# MCU_Sensors_CAN.net
KiCad netlist of a schematic drawn in Altium Designer
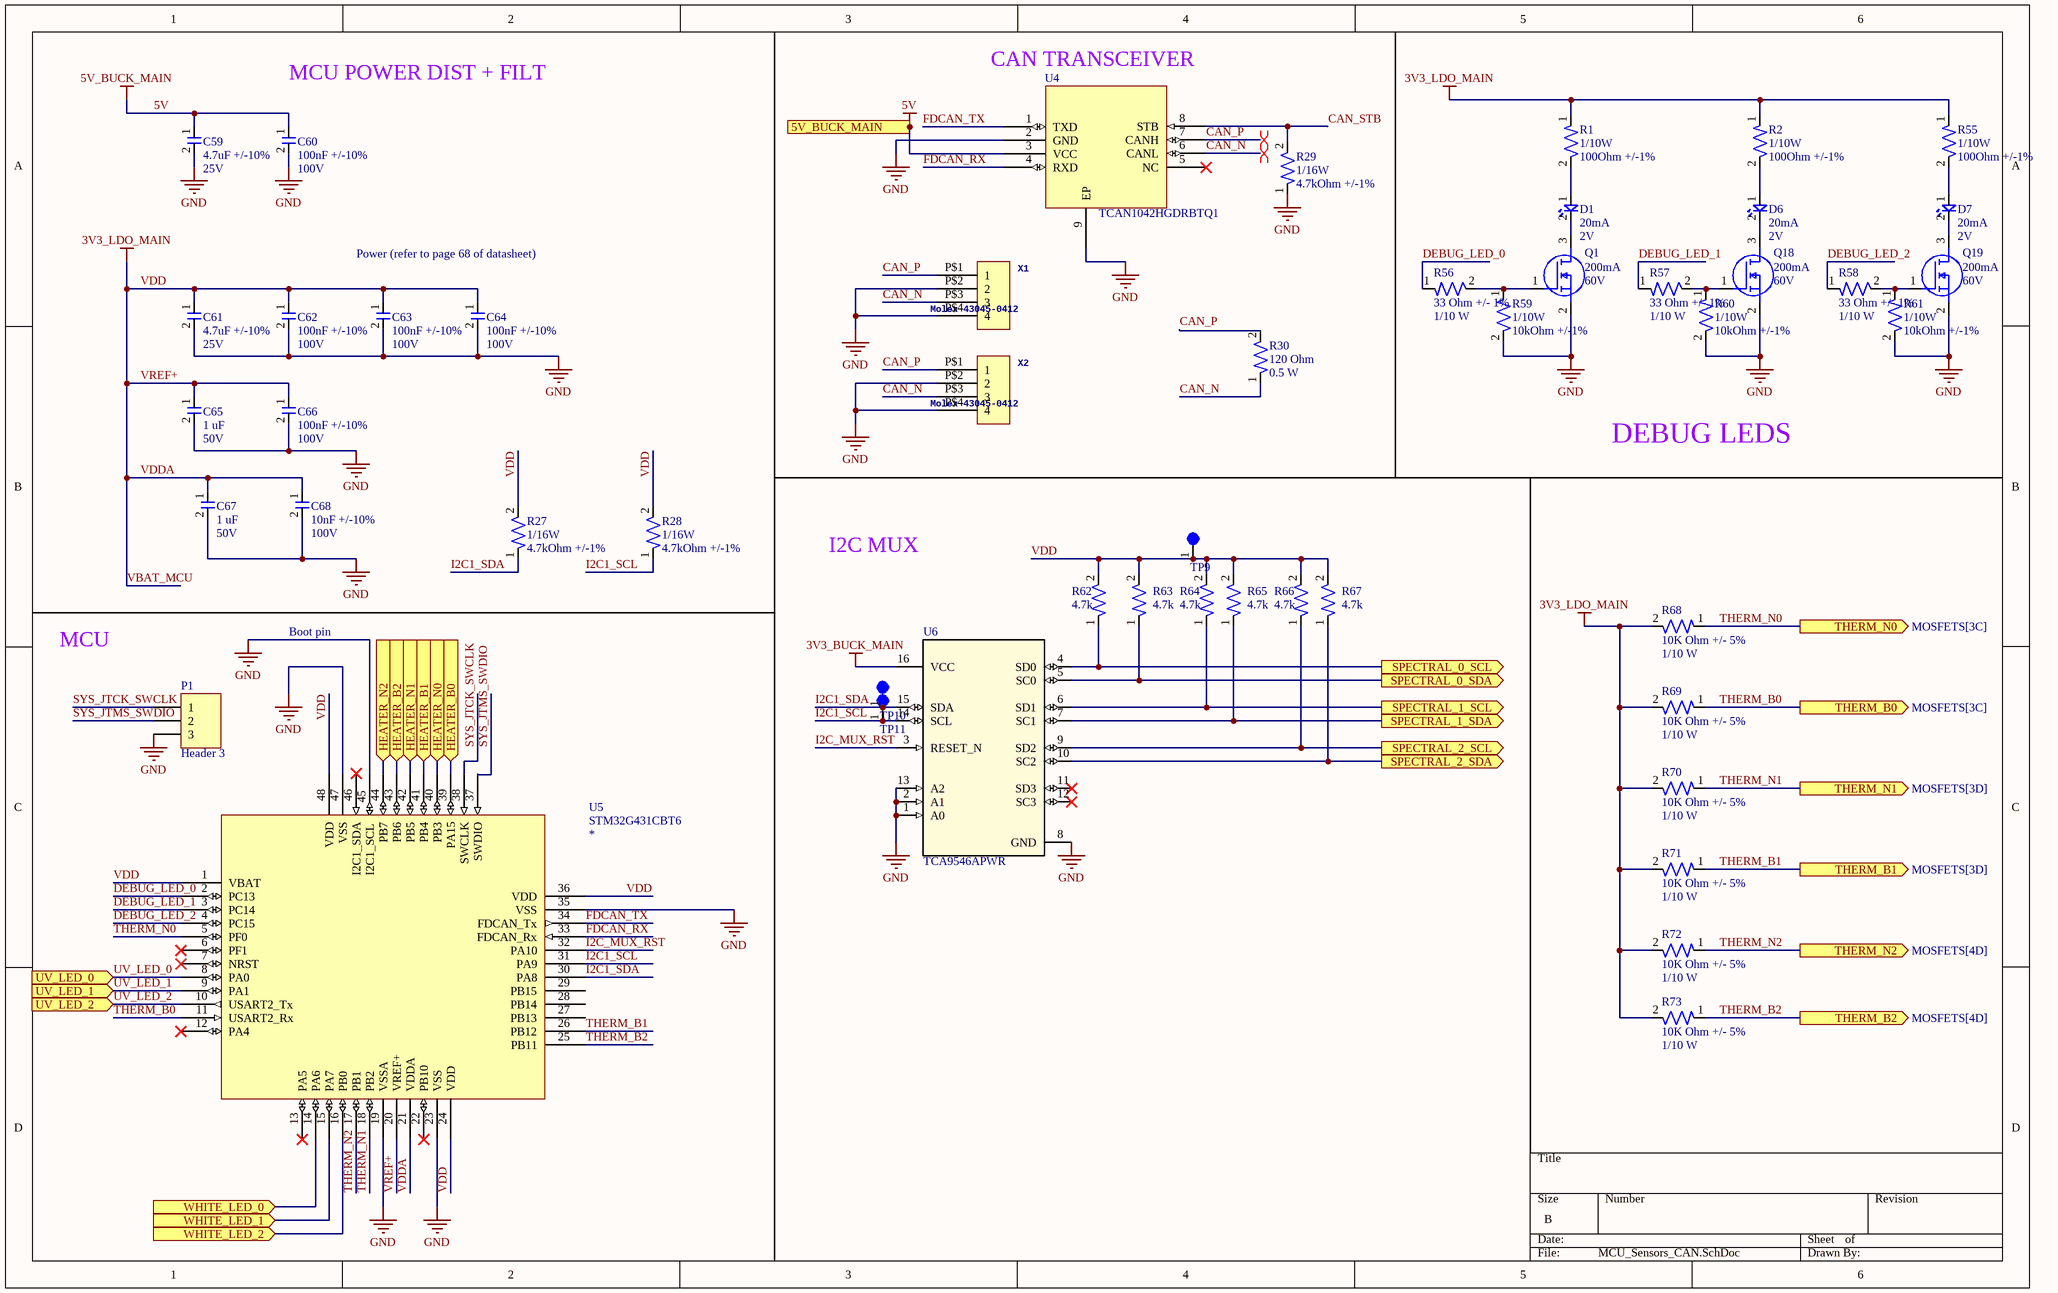
[diagram p0: MCU_Sensors_CAN.SchDoc]

(export (version "E")
  (design (tool "Eeschema 10.0.6"))
  (components
    (comp (ref "C59")
      (value "TMK107BBJ475KA-T")
      (footprint "CAP-0603")
      (description "4.7 µF ±10% 25V Ceramic Capacitor X5R 0603 (1608 Metric)")
      (fields
        (field (name "MANUFACTURER") "Taiyo Yuden")
        (field (name "CAPACITANCE") "4.7uF +/-10%")
        (field (name "VOLTAGE RATING") "25V")
      )
      (libsource (lib "MasterLib") (part "CAP-4.7U-0001"))
    )
    (comp (ref "C60")
      (value "CC0603KRX7R0BB104")
      (footprint "CAP-0603")
      (description "CAP CER 0.1UF 100V X7R 0603")
      (fields
        (field (name "MANUFACTURER") "YAGEO")
        (field (name "CAPACITANCE") "100nF +/-10%")
        (field (name "VOLTAGE RATING") "100V")
      )
      (libsource (lib "MasterLib") (part "CAP-100N-0001"))
    )
    (comp (ref "C61")
      (value "TMK107BBJ475KA-T")
      (footprint "CAP-0603")
      (description "4.7 µF ±10% 25V Ceramic Capacitor X5R 0603 (1608 Metric)")
      (fields
        (field (name "MANUFACTURER") "Taiyo Yuden")
        (field (name "CAPACITANCE") "4.7uF +/-10%")
        (field (name "VOLTAGE RATING") "25V")
      )
      (libsource (lib "MasterLib") (part "CAP-4.7U-0001"))
    )
    (comp (ref "C62")
      (value "CC0603KRX7R0BB104")
      (footprint "CAP-0603")
      (description "CAP CER 0.1UF 100V X7R 0603")
      (fields
        (field (name "MANUFACTURER") "YAGEO")
        (field (name "CAPACITANCE") "100nF +/-10%")
        (field (name "VOLTAGE RATING") "100V")
      )
      (libsource (lib "MasterLib") (part "CAP-100N-0001"))
    )
    (comp (ref "C63")
      (value "CC0603KRX7R0BB104")
      (footprint "CAP-0603")
      (description "CAP CER 0.1UF 100V X7R 0603")
      (fields
        (field (name "MANUFACTURER") "YAGEO")
        (field (name "CAPACITANCE") "100nF +/-10%")
        (field (name "VOLTAGE RATING") "100V")
      )
      (libsource (lib "MasterLib") (part "CAP-100N-0001"))
    )
    (comp (ref "C64")
      (value "CC0603KRX7R0BB104")
      (footprint "CAP-0603")
      (description "CAP CER 0.1UF 100V X7R 0603")
      (fields
        (field (name "MANUFACTURER") "YAGEO")
        (field (name "CAPACITANCE") "100nF +/-10%")
        (field (name "VOLTAGE RATING") "100V")
      )
      (libsource (lib "MasterLib") (part "CAP-100N-0001"))
    )
    (comp (ref "C65")
      (value "UMK107AB7105KA-T")
      (footprint "CAP-0603")
      (description "1 µF ±10% 50V Ceramic Capacitor X7R 0603 (1608 Metric)")
      (fields (field (name "CAPACITANCE") "1 uF") (field (name "VOLTAGE") "50V"))
      (libsource (lib "MasterLib") (part "CAP-1U-0002"))
    )
    (comp (ref "C66")
      (value "CC0603KRX7R0BB104")
      (footprint "CAP-0603")
      (description "CAP CER 0.1UF 100V X7R 0603")
      (fields
        (field (name "MANUFACTURER") "YAGEO")
        (field (name "CAPACITANCE") "100nF +/-10%")
        (field (name "VOLTAGE RATING") "100V")
      )
      (libsource (lib "MasterLib") (part "CAP-100N-0001"))
    )
    (comp (ref "C67")
      (value "UMK107AB7105KA-T")
      (footprint "CAP-0603")
      (description "1 µF ±10% 50V Ceramic Capacitor X7R 0603 (1608 Metric)")
      (fields (field (name "CAPACITANCE") "1 uF") (field (name "VOLTAGE") "50V"))
      (libsource (lib "MasterLib") (part "CAP-1U-0002"))
    )
    (comp (ref "C68")
      (value "CC0402KRX7R0BB103")
      (footprint "CAP-0402")
      (description "10000 pF ±10% 100V Ceramic Capacitor X7R 0402 (1005 Metric)")
      (fields
        (field (name "MANUFACTURER") "YAGEO")
        (field (name "CAPACITANCE") "10nF +/-10%")
        (field (name "VOLTAGE RATING") "100V")
      )
      (libsource (lib "MasterLib") (part "CAP-10N-0001"))
    )
    (comp (ref "D1")
      (value "150060AS75000")
      (footprint "LED-0603")
      (description "CAP CER 0.1UF 100V X7R 0603")
      (fields
        (field (name "MANUFACTURER") "Wurth Electronik")
        (field (name "CURRENT RATING") "20mA")
        (field (name "VF") "2V")
      )
      (libsource (lib "MasterLib") (part "LED_Amber_0001"))
    )
    (comp (ref "D6")
      (value "150060AS75000")
      (footprint "LED-0603")
      (description "CAP CER 0.1UF 100V X7R 0603")
      (fields
        (field (name "MANUFACTURER") "Wurth Electronik")
        (field (name "CURRENT RATING") "20mA")
        (field (name "VF") "2V")
      )
      (libsource (lib "MasterLib") (part "LED_Amber_0001"))
    )
    (comp (ref "D7")
      (value "150060AS75000")
      (footprint "LED-0603")
      (description "CAP CER 0.1UF 100V X7R 0603")
      (fields
        (field (name "MANUFACTURER") "Wurth Electronik")
        (field (name "CURRENT RATING") "20mA")
        (field (name "VF") "2V")
      )
      (libsource (lib "MasterLib") (part "LED_Amber_0001"))
    )
    (comp (ref "P1")
      (value "Header 3")
      (footprint "HDR1X3")
      (description "Header, 3-Pin")
      (fields (field (name "PUBLISHER") "Altium Limited"))
      (libsource (lib "Miscellaneous Connectors") (part "Header 3"))
    )
    (comp (ref "Q1")
      (value "T2N7002AK,LM")
      (footprint "NMOS-SOT23-3")
      (description "MOSFET N-CH 60V 200MA SOT23")
      (fields
        (field (name "MANUFACTURER") "Toshiba")
        (field (name "ID-CONTINUOUS") "200mA")
        (field (name "VDS-MAX") "60V")
      )
      (libsource (lib "MasterLib") (part "NMOS-200MA-0001"))
    )
    (comp (ref "Q18")
      (value "T2N7002AK,LM")
      (footprint "NMOS-SOT23-3")
      (description "MOSFET N-CH 60V 200MA SOT23")
      (fields
        (field (name "MANUFACTURER") "Toshiba")
        (field (name "ID-CONTINUOUS") "200mA")
        (field (name "VDS-MAX") "60V")
      )
      (libsource (lib "MasterLib") (part "NMOS-200MA-0001"))
    )
    (comp (ref "Q19")
      (value "T2N7002AK,LM")
      (footprint "NMOS-SOT23-3")
      (description "MOSFET N-CH 60V 200MA SOT23")
      (fields
        (field (name "MANUFACTURER") "Toshiba")
        (field (name "ID-CONTINUOUS") "200mA")
        (field (name "VDS-MAX") "60V")
      )
      (libsource (lib "MasterLib") (part "NMOS-200MA-0001"))
    )
    (comp (ref "R1")
      (value "AC0603FR-10100RL")
      (footprint "RES-0603")
      (description "100 Ohms ±1% 0.1W, 1/10W Chip Resistor 0603 (1608 Metric) Automotive AEC-Q200 Thick Film")
      (fields
        (field (name "MANUFACTURER") "YAGEO")
        (field (name "POWER RATING") "1/10W")
        (field (name "RESISTANCE") "100Ohm +/-1%")
      )
      (libsource (lib "MasterLib") (part "RES-100-0002"))
    )
    (comp (ref "R2")
      (value "AC0603FR-10100RL")
      (footprint "RES-0603")
      (description "100 Ohms ±1% 0.1W, 1/10W Chip Resistor 0603 (1608 Metric) Automotive AEC-Q200 Thick Film")
      (fields
        (field (name "MANUFACTURER") "YAGEO")
        (field (name "POWER RATING") "1/10W")
        (field (name "RESISTANCE") "100Ohm +/-1%")
      )
      (libsource (lib "MasterLib") (part "RES-100-0002"))
    )
    (comp (ref "R27")
      (value "RC0402FR-074K7P")
      (footprint "RES-0402")
      (description "RES SMD 4.7K OHM 1% 1/16W 0402")
      (fields
        (field (name "MANUFACTURER") "YAGEO")
        (field (name "POWER RATING") "1/16W")
        (field (name "RESISTANCE") "4.7kOhm +/-1%")
      )
      (libsource (lib "MasterLib") (part "RES-4.7K-0001"))
    )
    (comp (ref "R28")
      (value "RC0402FR-074K7P")
      (footprint "RES-0402")
      (description "RES SMD 4.7K OHM 1% 1/16W 0402")
      (fields
        (field (name "MANUFACTURER") "YAGEO")
        (field (name "POWER RATING") "1/16W")
        (field (name "RESISTANCE") "4.7kOhm +/-1%")
      )
      (libsource (lib "MasterLib") (part "RES-4.7K-0001"))
    )
    (comp (ref "R29")
      (value "RC0402FR-074K7P")
      (footprint "RES-0402")
      (description "RES SMD 4.7K OHM 1% 1/16W 0402")
      (fields
        (field (name "MANUFACTURER") "YAGEO")
        (field (name "POWER RATING") "1/16W")
        (field (name "RESISTANCE") "4.7kOhm +/-1%")
      )
      (libsource (lib "MasterLib") (part "RES-4.7K-0001"))
    )
    (comp (ref "R30")
      (value "CRGH1206F120R")
      (footprint "RES-1206")
      (description "120 Ohms ±1% 0.5W, 1/2W Chip Resistor 1206 (3216 Metric) Thick Film")
      (fields
        (field (name "TOLERANCE") "1%")
        (field (name "RESISTANCE") "120 Ohm")
        (field (name "POWER") "0.5 W")
      )
      (libsource (lib "MasterLib") (part "RES-120-0002"))
    )
    (comp (ref "R55")
      (value "AC0603FR-10100RL")
      (footprint "RES-0603")
      (description "100 Ohms ±1% 0.1W, 1/10W Chip Resistor 0603 (1608 Metric) Automotive AEC-Q200 Thick Film")
      (fields
        (field (name "MANUFACTURER") "YAGEO")
        (field (name "POWER RATING") "1/10W")
        (field (name "RESISTANCE") "100Ohm +/-1%")
      )
      (libsource (lib "MasterLib") (part "RES-100-0002"))
    )
    (comp (ref "R56")
      (value "ERJ2RKF33R0X")
      (footprint "RES-0402")
      (description "100mW Thick Film Resistors ±100ppm/℃ ±1% -55℃~+155℃ 33Ω 0402  Chip Resistor - Surface Mount ROHS")
      (fields
        (field (name "RESISTANCE") "33 Ohm +/- 1%")
        (field (name "POWER") "1/10 W")
        (field (name "JLC PART NUMBER") "C278594")
      )
      (libsource (lib "MasterLib") (part "RES-33-0003-JLC"))
    )
    (comp (ref "R57")
      (value "ERJ2RKF33R0X")
      (footprint "RES-0402")
      (description "100mW Thick Film Resistors ±100ppm/℃ ±1% -55℃~+155℃ 33Ω 0402  Chip Resistor - Surface Mount ROHS")
      (fields
        (field (name "RESISTANCE") "33 Ohm +/- 1%")
        (field (name "POWER") "1/10 W")
        (field (name "JLC PART NUMBER") "C278594")
      )
      (libsource (lib "MasterLib") (part "RES-33-0003-JLC"))
    )
    (comp (ref "R58")
      (value "ERJ2RKF33R0X")
      (footprint "RES-0402")
      (description "100mW Thick Film Resistors ±100ppm/℃ ±1% -55℃~+155℃ 33Ω 0402  Chip Resistor - Surface Mount ROHS")
      (fields
        (field (name "RESISTANCE") "33 Ohm +/- 1%")
        (field (name "POWER") "1/10 W")
        (field (name "JLC PART NUMBER") "C278594")
      )
      (libsource (lib "MasterLib") (part "RES-33-0003-JLC"))
    )
    (comp (ref "R59")
      (value "RC0603FR-0710KP")
      (footprint "RES-0603")
      (description "RES SMD 10K OHM 1% 1/10W 0603")
      (fields
        (field (name "MANUFACTURER") "YAGEO")
        (field (name "POWER RATING") "1/10W")
        (field (name "RESISTANCE") "10kOhm +/-1%")
      )
      (libsource (lib "MasterLib") (part "RES-10K-0002"))
    )
    (comp (ref "R60")
      (value "RC0603FR-0710KP")
      (footprint "RES-0603")
      (description "RES SMD 10K OHM 1% 1/10W 0603")
      (fields
        (field (name "MANUFACTURER") "YAGEO")
        (field (name "POWER RATING") "1/10W")
        (field (name "RESISTANCE") "10kOhm +/-1%")
      )
      (libsource (lib "MasterLib") (part "RES-10K-0002"))
    )
    (comp (ref "R61")
      (value "RC0603FR-0710KP")
      (footprint "RES-0603")
      (description "RES SMD 10K OHM 1% 1/10W 0603")
      (fields
        (field (name "MANUFACTURER") "YAGEO")
        (field (name "POWER RATING") "1/10W")
        (field (name "RESISTANCE") "10kOhm +/-1%")
      )
      (libsource (lib "MasterLib") (part "RES-10K-0002"))
    )
    (comp (ref "R62")
      (value "RC0402FR-074K7P")
      (footprint "RES-0402")
      (description "RES SMD 4.7K OHM 1% 1/16W 0402")
      (fields (field (name "MANUFACTURER") "YAGEO") (field (name "RESISTANCE") "4.7k"))
      (libsource (lib "MasterLib") (part "RES-4.7K-0001"))
    )
    (comp (ref "R63")
      (value "RC0402FR-074K7P")
      (footprint "RES-0402")
      (description "RES SMD 4.7K OHM 1% 1/16W 0402")
      (fields (field (name "MANUFACTURER") "YAGEO") (field (name "RESISTANCE") "4.7k"))
      (libsource (lib "MasterLib") (part "RES-4.7K-0001"))
    )
    (comp (ref "R64")
      (value "RC0402FR-074K7P")
      (footprint "RES-0402")
      (description "RES SMD 4.7K OHM 1% 1/16W 0402")
      (fields (field (name "MANUFACTURER") "YAGEO") (field (name "RESISTANCE") "4.7k"))
      (libsource (lib "MasterLib") (part "RES-4.7K-0001"))
    )
    (comp (ref "R65")
      (value "RC0402FR-074K7P")
      (footprint "RES-0402")
      (description "RES SMD 4.7K OHM 1% 1/16W 0402")
      (fields (field (name "MANUFACTURER") "YAGEO") (field (name "RESISTANCE") "4.7k"))
      (libsource (lib "MasterLib") (part "RES-4.7K-0001"))
    )
    (comp (ref "R66")
      (value "RC0402FR-074K7P")
      (footprint "RES-0402")
      (description "RES SMD 4.7K OHM 1% 1/16W 0402")
      (fields (field (name "MANUFACTURER") "YAGEO") (field (name "RESISTANCE") "4.7k"))
      (libsource (lib "MasterLib") (part "RES-4.7K-0001"))
    )
    (comp (ref "R67")
      (value "RC0402FR-074K7P")
      (footprint "RES-0402")
      (description "RES SMD 4.7K OHM 1% 1/16W 0402")
      (fields (field (name "MANUFACTURER") "YAGEO") (field (name "RESISTANCE") "4.7k"))
      (libsource (lib "MasterLib") (part "RES-4.7K-0001"))
    )
    (comp (ref "R68")
      (value "ERJ2GEJ103X")
      (footprint "RES-0402")
      (fields
        (field (name "RESISTANCE") "10K Ohm +/- 5%")
        (field (name "POWER") "1/10 W")
        (field (name "JLC PART NUMBER") "C278577")
      )
      (libsource (lib "MasterLib") (part "RES-10K-0003-JLC"))
    )
    (comp (ref "R69")
      (value "ERJ2GEJ103X")
      (footprint "RES-0402")
      (fields
        (field (name "RESISTANCE") "10K Ohm +/- 5%")
        (field (name "POWER") "1/10 W")
        (field (name "JLC PART NUMBER") "C278577")
      )
      (libsource (lib "MasterLib") (part "RES-10K-0003-JLC"))
    )
    (comp (ref "R70")
      (value "ERJ2GEJ103X")
      (footprint "RES-0402")
      (fields
        (field (name "RESISTANCE") "10K Ohm +/- 5%")
        (field (name "POWER") "1/10 W")
        (field (name "JLC PART NUMBER") "C278577")
      )
      (libsource (lib "MasterLib") (part "RES-10K-0003-JLC"))
    )
    (comp (ref "R71")
      (value "ERJ2GEJ103X")
      (footprint "RES-0402")
      (fields
        (field (name "RESISTANCE") "10K Ohm +/- 5%")
        (field (name "POWER") "1/10 W")
        (field (name "JLC PART NUMBER") "C278577")
      )
      (libsource (lib "MasterLib") (part "RES-10K-0003-JLC"))
    )
    (comp (ref "R72")
      (value "ERJ2GEJ103X")
      (footprint "RES-0402")
      (fields
        (field (name "RESISTANCE") "10K Ohm +/- 5%")
        (field (name "POWER") "1/10 W")
        (field (name "JLC PART NUMBER") "C278577")
      )
      (libsource (lib "MasterLib") (part "RES-10K-0003-JLC"))
    )
    (comp (ref "R73")
      (value "ERJ2GEJ103X")
      (footprint "RES-0402")
      (fields
        (field (name "RESISTANCE") "10K Ohm +/- 5%")
        (field (name "POWER") "1/10 W")
        (field (name "JLC PART NUMBER") "C278577")
      )
      (libsource (lib "MasterLib") (part "RES-10K-0003-JLC"))
    )
    (comp (ref "TP9")
      (value "5003")
      (footprint "TEST-POINT-0001")
      (description "Oranange PC Test Point, Miniature Phoisphor Bronze Silver Plating Through Hole Mounting Type")
      (libsource (lib "MasterLib") (part "TEST-POINT-0001"))
    )
    (comp (ref "TP10")
      (value "5003")
      (footprint "TEST-POINT-0001")
      (description "Oranange PC Test Point, Miniature Phoisphor Bronze Silver Plating Through Hole Mounting Type")
      (libsource (lib "MasterLib") (part "TEST-POINT-0001"))
    )
    (comp (ref "TP11")
      (value "5003")
      (footprint "TEST-POINT-0001")
      (description "Oranange PC Test Point, Miniature Phoisphor Bronze Silver Plating Through Hole Mounting Type")
      (libsource (lib "MasterLib") (part "TEST-POINT-0001"))
    )
    (comp (ref "U4")
      (value "TCAN1042HGDRBTQ1")
      (footprint "IC-8-VSON")
      (description "1/1 Transceiver CANbus 8-VSON (3x3)")
      (fields (field (name "MANUFACTURER") "Texas Instrument"))
      (libsource (lib "MasterLib") (part "IC-CAN-TRANSCEIVER-0002"))
    )
    (comp (ref "U5")
      (value "STM32G431CBT6")
      (footprint "LQFP48-7x7mm")
      (fields (field (name "PARAMETER 1") "*"))
      (libsource (lib "MasterLib") (part "IC-STM32G431CBT6-0001"))
    )
    (comp (ref "U6")
      (value "TCA9546APWR")
      (footprint "PW0016A-IPC_A")
      (description "Multiplexer Switch ICs I2C SWITCH 4CH")
      (fields (field (name "COPYRIGHT") "Copyright (C) 2023 Ultra Librarian. All rights reserved."))
      (libsource (lib "MasterLib") (part "IC-MUX-0003"))
    )
    (comp (ref "X1")
      (value "Molex 43045-0412")
      (footprint "43045-0412")
      (libsource (lib "Molex Microfit") (part "Micro-Fit Molex 4 Pin 2 Row Vertical"))
    )
    (comp (ref "X2")
      (value "Molex 43045-0412")
      (footprint "43045-0412")
      (libsource (lib "Molex Microfit") (part "Micro-Fit Molex 4 Pin 2 Row Vertical"))
    )
  )
  (nets
    (net (code "2") (name "/CAN_N") (class "Default")
      (node (ref "R30") (pin "1") (pinfunction "1_1") (pintype "passive"))
      (node (ref "U4") (pin "6") (pinfunction "CANL_6") (pintype "bidirectional"))
      (node (ref "X1") (pin "P$3") (pinfunction "3_P$3") (pintype "passive"))
      (node (ref "X2") (pin "P$3") (pinfunction "3_P$3") (pintype "passive"))
    )
    (net (code "3") (name "/CAN_P") (class "Default")
      (node (ref "R30") (pin "2") (pinfunction "2_2") (pintype "passive"))
      (node (ref "U4") (pin "7") (pinfunction "CANH_7") (pintype "bidirectional"))
      (node (ref "X1") (pin "P$1") (pinfunction "1_P$1") (pintype "passive"))
      (node (ref "X2") (pin "P$1") (pinfunction "1_P$1") (pintype "passive"))
    )
    (net (code "4") (name "/CAN_STB") (class "Default")
      (node (ref "R29") (pin "2") (pinfunction "2_2") (pintype "passive"))
      (node (ref "U4") (pin "8") (pinfunction "STB_8") (pintype "input"))
    )
    (net (code "5") (name "/DEBUG_LED_0") (class "Default")
      (node (ref "R56") (pin "1") (pinfunction "1_1") (pintype "passive"))
      (node (ref "U5") (pin "2") (pinfunction "PC13_2") (pintype "bidirectional"))
    )
    (net (code "6") (name "/DEBUG_LED_1") (class "Default")
      (node (ref "R57") (pin "1") (pinfunction "1_1") (pintype "passive"))
      (node (ref "U5") (pin "3") (pinfunction "PC14_3") (pintype "bidirectional"))
    )
    (net (code "7") (name "/DEBUG_LED_2") (class "Default")
      (node (ref "R58") (pin "1") (pinfunction "1_1") (pintype "passive"))
      (node (ref "U5") (pin "4") (pinfunction "PC15_4") (pintype "bidirectional"))
    )
    (net (code "8") (name "/FDCAN_RX") (class "Default")
      (node (ref "U4") (pin "4") (pinfunction "RXD_4") (pintype "bidirectional"))
      (node (ref "U5") (pin "33") (pinfunction "FDCAN_Rx_33") (pintype "input"))
    )
    (net (code "9") (name "/FDCAN_TX") (class "Default")
      (node (ref "U4") (pin "1") (pinfunction "TXD_1") (pintype "bidirectional"))
      (node (ref "U5") (pin "34") (pinfunction "FDCAN_Tx_34") (pintype "output"))
    )
    (net (code "10") (name "/HEATER_B0") (class "Default")
      (node (ref "U5") (pin "39") (pinfunction "PA15_39") (pintype "bidirectional"))
    )
    (net (code "11") (name "/HEATER_B1") (class "Default")
      (node (ref "U5") (pin "41") (pinfunction "PB4_41") (pintype "bidirectional"))
    )
    (net (code "12") (name "/HEATER_B2") (class "Default")
      (node (ref "U5") (pin "43") (pinfunction "PB6_43") (pintype "bidirectional"))
    )
    (net (code "13") (name "/HEATER_N0") (class "Default")
      (node (ref "U5") (pin "40") (pinfunction "PB3_40") (pintype "bidirectional"))
    )
    (net (code "14") (name "/HEATER_N1") (class "Default")
      (node (ref "U5") (pin "42") (pinfunction "PB5_42") (pintype "bidirectional"))
    )
    (net (code "15") (name "/HEATER_N2") (class "Default")
      (node (ref "U5") (pin "44") (pinfunction "PB7_44") (pintype "bidirectional"))
    )
    (net (code "16") (name "/I2C1_SCL") (class "Default")
      (node (ref "R28") (pin "1") (pinfunction "1_1") (pintype "passive"))
      (node (ref "TP11") (pin "1") (pinfunction "0_1") (pintype "passive"))
      (node (ref "U5") (pin "31") (pinfunction "PA9_31") (pintype "power_in"))
      (node (ref "U6") (pin "14") (pinfunction "SCL_14") (pintype "bidirectional"))
    )
    (net (code "17") (name "/I2C1_SDA") (class "Default")
      (node (ref "R27") (pin "1") (pinfunction "1_1") (pintype "passive"))
      (node (ref "TP10") (pin "1") (pinfunction "0_1") (pintype "passive"))
      (node (ref "U5") (pin "30") (pinfunction "PA8_30") (pintype "power_in"))
      (node (ref "U6") (pin "15") (pinfunction "SDA_15") (pintype "bidirectional"))
    )
    (net (code "18") (name "/I2C_MUX_RST") (class "Default")
      (node (ref "U5") (pin "32") (pinfunction "PA10_32") (pintype "power_in"))
      (node (ref "U6") (pin "3") (pinfunction "RESET_N_3") (pintype "input"))
    )
    (net (code "19") (name "/SPECTRAL_0_SCL") (class "Default")
      (node (ref "R62") (pin "1") (pinfunction "1_1") (pintype "passive"))
      (node (ref "U6") (pin "4") (pinfunction "SD0_4") (pintype "bidirectional"))
    )
    (net (code "20") (name "/SPECTRAL_0_SDA") (class "Default")
      (node (ref "R63") (pin "1") (pinfunction "1_1") (pintype "passive"))
      (node (ref "U6") (pin "5") (pinfunction "SC0_5") (pintype "bidirectional"))
    )
    (net (code "21") (name "/SPECTRAL_1_SCL") (class "Default")
      (node (ref "R64") (pin "1") (pinfunction "1_1") (pintype "passive"))
      (node (ref "U6") (pin "6") (pinfunction "SD1_6") (pintype "bidirectional"))
    )
    (net (code "22") (name "/SPECTRAL_1_SDA") (class "Default")
      (node (ref "R65") (pin "1") (pinfunction "1_1") (pintype "passive"))
      (node (ref "U6") (pin "7") (pinfunction "SC1_7") (pintype "bidirectional"))
    )
    (net (code "23") (name "/SPECTRAL_2_SCL") (class "Default")
      (node (ref "R66") (pin "1") (pinfunction "1_1") (pintype "passive"))
      (node (ref "U6") (pin "9") (pinfunction "SD2_9") (pintype "bidirectional"))
    )
    (net (code "24") (name "/SPECTRAL_2_SDA") (class "Default")
      (node (ref "R67") (pin "1") (pinfunction "1_1") (pintype "passive"))
      (node (ref "U6") (pin "10") (pinfunction "SC2_10") (pintype "bidirectional"))
    )
    (net (code "25") (name "/SYS_JTCK_SWCLK") (class "Default")
      (node (ref "P1") (pin "1") (pinfunction "1_1") (pintype "passive"))
      (node (ref "U5") (pin "38") (pinfunction "SWCLK_38") (pintype "input"))
    )
    (net (code "26") (name "/SYS_JTMS_SWDIO") (class "Default")
      (node (ref "P1") (pin "2") (pinfunction "2_2") (pintype "passive"))
      (node (ref "U5") (pin "37") (pinfunction "SWDIO_37") (pintype "input"))
    )
    (net (code "27") (name "/THERM_B0") (class "Default")
      (node (ref "R69") (pin "1") (pinfunction "1_1") (pintype "passive"))
      (node (ref "U5") (pin "11") (pinfunction "USART2_Rx_11") (pintype "input"))
    )
    (net (code "28") (name "/THERM_B1") (class "Default")
      (node (ref "R71") (pin "1") (pinfunction "1_1") (pintype "passive"))
      (node (ref "U5") (pin "26") (pinfunction "PB12_26") (pintype "power_in"))
    )
    (net (code "29") (name "/THERM_B2") (class "Default")
      (node (ref "R73") (pin "1") (pinfunction "1_1") (pintype "passive"))
      (node (ref "U5") (pin "25") (pinfunction "PB11_25") (pintype "power_in"))
    )
    (net (code "30") (name "/THERM_N0") (class "Default")
      (node (ref "R68") (pin "1") (pinfunction "1_1") (pintype "passive"))
      (node (ref "U5") (pin "5") (pinfunction "PF0_5") (pintype "bidirectional"))
    )
    (net (code "31") (name "/THERM_N1") (class "Default")
      (node (ref "R70") (pin "1") (pinfunction "1_1") (pintype "passive"))
      (node (ref "U5") (pin "18") (pinfunction "PB2_18") (pintype "bidirectional"))
    )
    (net (code "32") (name "/THERM_N2") (class "Default")
      (node (ref "R72") (pin "1") (pinfunction "1_1") (pintype "passive"))
      (node (ref "U5") (pin "17") (pinfunction "PB1_17") (pintype "bidirectional"))
    )
    (net (code "33") (name "/UV_LED_0") (class "Default")
      (node (ref "U5") (pin "8") (pinfunction "PA0_8") (pintype "bidirectional"))
    )
    (net (code "34") (name "/UV_LED_1") (class "Default")
      (node (ref "U5") (pin "9") (pinfunction "PA1_9") (pintype "bidirectional"))
    )
    (net (code "35") (name "/UV_LED_2") (class "Default")
      (node (ref "U5") (pin "10") (pinfunction "USART2_Tx_10") (pintype "output"))
    )
    (net (code "36") (name "/WHITE_LED_0") (class "Default")
      (node (ref "U5") (pin "14") (pinfunction "PA6_14") (pintype "bidirectional"))
    )
    (net (code "37") (name "/WHITE_LED_1") (class "Default")
      (node (ref "U5") (pin "15") (pinfunction "PA7_15") (pintype "bidirectional"))
    )
    (net (code "38") (name "/WHITE_LED_2") (class "Default")
      (node (ref "U5") (pin "16") (pinfunction "PB0_16") (pintype "bidirectional"))
    )
    (net (code "39") (name "3V3_BUCK_MAIN") (class "Default")
      (node (ref "U6") (pin "16") (pinfunction "VCC_16") (pintype "power_in"))
    )
    (net (code "40") (name "3V3_LDO_MAIN") (class "Default")
      (node (ref "C61") (pin "1") (pinfunction "1_1") (pintype "passive"))
      (node (ref "C62") (pin "1") (pinfunction "1_1") (pintype "passive"))
      (node (ref "C63") (pin "1") (pinfunction "1_1") (pintype "passive"))
      (node (ref "C64") (pin "1") (pinfunction "1_1") (pintype "passive"))
      (node (ref "C65") (pin "1") (pinfunction "1_1") (pintype "passive"))
      (node (ref "C66") (pin "1") (pinfunction "1_1") (pintype "passive"))
      (node (ref "C67") (pin "1") (pinfunction "1_1") (pintype "passive"))
      (node (ref "C68") (pin "1") (pinfunction "1_1") (pintype "passive"))
      (node (ref "R1") (pin "1") (pinfunction "1_1") (pintype "passive"))
      (node (ref "R2") (pin "1") (pinfunction "1_1") (pintype "passive"))
      (node (ref "R27") (pin "2") (pinfunction "2_2") (pintype "passive"))
      (node (ref "R28") (pin "2") (pinfunction "2_2") (pintype "passive"))
      (node (ref "R55") (pin "1") (pinfunction "1_1") (pintype "passive"))
      (node (ref "R62") (pin "2") (pinfunction "2_2") (pintype "passive"))
      (node (ref "R63") (pin "2") (pinfunction "2_2") (pintype "passive"))
      (node (ref "R64") (pin "2") (pinfunction "2_2") (pintype "passive"))
      (node (ref "R65") (pin "2") (pinfunction "2_2") (pintype "passive"))
      (node (ref "R66") (pin "2") (pinfunction "2_2") (pintype "passive"))
      (node (ref "R67") (pin "2") (pinfunction "2_2") (pintype "passive"))
      (node (ref "R68") (pin "2") (pinfunction "2_2") (pintype "passive"))
      (node (ref "R69") (pin "2") (pinfunction "2_2") (pintype "passive"))
      (node (ref "R70") (pin "2") (pinfunction "2_2") (pintype "passive"))
      (node (ref "R71") (pin "2") (pinfunction "2_2") (pintype "passive"))
      (node (ref "R72") (pin "2") (pinfunction "2_2") (pintype "passive"))
      (node (ref "R73") (pin "2") (pinfunction "2_2") (pintype "passive"))
      (node (ref "TP9") (pin "1") (pinfunction "0_1") (pintype "passive"))
      (node (ref "U5") (pin "1") (pinfunction "VBAT_1") (pintype "power_in"))
      (node (ref "U5") (pin "20") (pinfunction "VREF+_20") (pintype "power_in"))
      (node (ref "U5") (pin "21") (pinfunction "VDDA_21") (pintype "power_in"))
      (node (ref "U5") (pin "24") (pinfunction "VDD_24") (pintype "power_in"))
      (node (ref "U5") (pin "36") (pinfunction "VDD_36") (pintype "power_in"))
      (node (ref "U5") (pin "48") (pinfunction "VDD_48") (pintype "power_in"))
    )
    (net (code "41") (name "5V") (class "Default")
      (node (ref "C59") (pin "1") (pinfunction "1_1") (pintype "passive"))
      (node (ref "C60") (pin "1") (pinfunction "1_1") (pintype "passive"))
      (node (ref "U4") (pin "3") (pinfunction "VCC_3") (pintype "power_in"))
    )
    (net (code "42") (name "GND") (class "Default")
      (node (ref "C59") (pin "2") (pinfunction "2_2") (pintype "passive"))
      (node (ref "C60") (pin "2") (pinfunction "2_2") (pintype "passive"))
      (node (ref "C61") (pin "2") (pinfunction "2_2") (pintype "passive"))
      (node (ref "C62") (pin "2") (pinfunction "2_2") (pintype "passive"))
      (node (ref "C63") (pin "2") (pinfunction "2_2") (pintype "passive"))
      (node (ref "C64") (pin "2") (pinfunction "2_2") (pintype "passive"))
      (node (ref "C65") (pin "2") (pinfunction "2_2") (pintype "passive"))
      (node (ref "C66") (pin "2") (pinfunction "2_2") (pintype "passive"))
      (node (ref "C67") (pin "2") (pinfunction "2_2") (pintype "passive"))
      (node (ref "C68") (pin "2") (pinfunction "2_2") (pintype "passive"))
      (node (ref "P1") (pin "3") (pinfunction "3_3") (pintype "passive"))
      (node (ref "Q1") (pin "2") (pinfunction "S_2") (pintype "passive"))
      (node (ref "Q18") (pin "2") (pinfunction "S_2") (pintype "passive"))
      (node (ref "Q19") (pin "2") (pinfunction "S_2") (pintype "passive"))
      (node (ref "R29") (pin "1") (pinfunction "1_1") (pintype "passive"))
      (node (ref "R59") (pin "2") (pinfunction "2_2") (pintype "passive"))
      (node (ref "R60") (pin "2") (pinfunction "2_2") (pintype "passive"))
      (node (ref "R61") (pin "2") (pinfunction "2_2") (pintype "passive"))
      (node (ref "U4") (pin "2") (pinfunction "GND_2") (pintype "power_in"))
      (node (ref "U4") (pin "9") (pinfunction "EP_9") (pintype "power_in"))
      (node (ref "U5") (pin "19") (pinfunction "VSSA_19") (pintype "power_in"))
      (node (ref "U5") (pin "23") (pinfunction "VSS_23") (pintype "power_in"))
      (node (ref "U5") (pin "35") (pinfunction "VSS_35") (pintype "power_in"))
      (node (ref "U5") (pin "45") (pinfunction "I2C1_SCL_45") (pintype "bidirectional"))
      (node (ref "U5") (pin "47") (pinfunction "VSS_47") (pintype "power_in"))
      (node (ref "U6") (pin "1") (pinfunction "A0_1") (pintype "input"))
      (node (ref "U6") (pin "13") (pinfunction "A2_13") (pintype "input"))
      (node (ref "U6") (pin "2") (pinfunction "A1_2") (pintype "input"))
      (node (ref "U6") (pin "8") (pinfunction "GND_8") (pintype "power_in"))
      (node (ref "X1") (pin "P$2") (pinfunction "2_P$2") (pintype "passive"))
      (node (ref "X1") (pin "P$4") (pinfunction "4_P$4") (pintype "passive"))
      (node (ref "X2") (pin "P$2") (pinfunction "2_P$2") (pintype "passive"))
      (node (ref "X2") (pin "P$4") (pinfunction "4_P$4") (pintype "passive"))
    )
    (net (code "43") (name "Net-(D1-Pad1)") (class "Default")
      (node (ref "D1") (pin "1") (pinfunction "1_1") (pintype "passive"))
      (node (ref "R1") (pin "2") (pinfunction "2_2") (pintype "passive"))
    )
    (net (code "44") (name "Net-(D6-Pad1)") (class "Default")
      (node (ref "D6") (pin "1") (pinfunction "1_1") (pintype "passive"))
      (node (ref "R2") (pin "2") (pinfunction "2_2") (pintype "passive"))
    )
    (net (code "45") (name "Net-(D7-Pad1)") (class "Default")
      (node (ref "D7") (pin "1") (pinfunction "1_1") (pintype "passive"))
      (node (ref "R55") (pin "2") (pinfunction "2_2") (pintype "passive"))
    )
    (net (code "46") (name "Net-(Q1-D)") (class "Default")
      (node (ref "D1") (pin "2") (pinfunction "2_2") (pintype "passive"))
      (node (ref "Q1") (pin "3") (pinfunction "D_3") (pintype "passive"))
    )
    (net (code "47") (name "Net-(Q1-G)") (class "Default")
      (node (ref "Q1") (pin "1") (pinfunction "G_1") (pintype "passive"))
      (node (ref "R56") (pin "2") (pinfunction "2_2") (pintype "passive"))
      (node (ref "R59") (pin "1") (pinfunction "1_1") (pintype "passive"))
    )
    (net (code "48") (name "Net-(Q18-D)") (class "Default")
      (node (ref "D6") (pin "2") (pinfunction "2_2") (pintype "passive"))
      (node (ref "Q18") (pin "3") (pinfunction "D_3") (pintype "passive"))
    )
    (net (code "49") (name "Net-(Q18-G)") (class "Default")
      (node (ref "Q18") (pin "1") (pinfunction "G_1") (pintype "passive"))
      (node (ref "R57") (pin "2") (pinfunction "2_2") (pintype "passive"))
      (node (ref "R60") (pin "1") (pinfunction "1_1") (pintype "passive"))
    )
    (net (code "50") (name "Net-(Q19-D)") (class "Default")
      (node (ref "D7") (pin "2") (pinfunction "2_2") (pintype "passive"))
      (node (ref "Q19") (pin "3") (pinfunction "D_3") (pintype "passive"))
    )
    (net (code "51") (name "Net-(Q19-G)") (class "Default")
      (node (ref "Q19") (pin "1") (pinfunction "G_1") (pintype "passive"))
      (node (ref "R58") (pin "2") (pinfunction "2_2") (pintype "passive"))
      (node (ref "R61") (pin "1") (pinfunction "1_1") (pintype "passive"))
    )
    (net (code "52") (name "unconnected-(U4-NC-Pad5)") (class "Default")
      (node (ref "U4") (pin "5") (pinfunction "NC_5") (pintype "power_in+no_connect"))
    )
    (net (code "53") (name "unconnected-(U5-I2C1_SDA-Pad46)") (class "Default")
      (node (ref "U5") (pin "46") (pinfunction "I2C1_SDA_46") (pintype "input+no_connect"))
    )
    (net (code "54") (name "unconnected-(U5-NRST-Pad7)") (class "Default")
      (node (ref "U5") (pin "7") (pinfunction "NRST_7") (pintype "bidirectional+no_connect"))
    )
    (net (code "55") (name "unconnected-(U5-PA4-Pad12)") (class "Default")
      (node (ref "U5") (pin "12") (pinfunction "PA4_12") (pintype "bidirectional+no_connect"))
    )
    (net (code "56") (name "unconnected-(U5-PA5-Pad13)") (class "Default")
      (node (ref "U5") (pin "13") (pinfunction "PA5_13") (pintype "bidirectional+no_connect"))
    )
    (net (code "57") (name "unconnected-(U5-PB10-Pad22)") (class "Default")
      (node (ref "U5") (pin "22") (pinfunction "PB10_22") (pintype "bidirectional+no_connect"))
    )
    (net (code "58") (name "unconnected-(U5-PB13-Pad27)") (class "Default")
      (node (ref "U5") (pin "27") (pinfunction "PB13_27") (pintype "power_in"))
    )
    (net (code "59") (name "unconnected-(U5-PB14-Pad28)") (class "Default")
      (node (ref "U5") (pin "28") (pinfunction "PB14_28") (pintype "power_in"))
    )
    (net (code "60") (name "unconnected-(U5-PB15-Pad29)") (class "Default")
      (node (ref "U5") (pin "29") (pinfunction "PB15_29") (pintype "power_in"))
    )
    (net (code "61") (name "unconnected-(U5-PF1-Pad6)") (class "Default")
      (node (ref "U5") (pin "6") (pinfunction "PF1_6") (pintype "bidirectional+no_connect"))
    )
    (net (code "62") (name "unconnected-(U6-SC3-Pad12)") (class "Default")
      (node (ref "U6") (pin "12") (pinfunction "SC3_12") (pintype "bidirectional+no_connect"))
    )
    (net (code "63") (name "unconnected-(U6-SD3-Pad11)") (class "Default")
      (node (ref "U6") (pin "11") (pinfunction "SD3_11") (pintype "bidirectional+no_connect"))
    )
  )
)
